# ESP-32-UNICLOCK-Nixi-V2.net
KiCad netlist of a schematic drawn in EAGLE
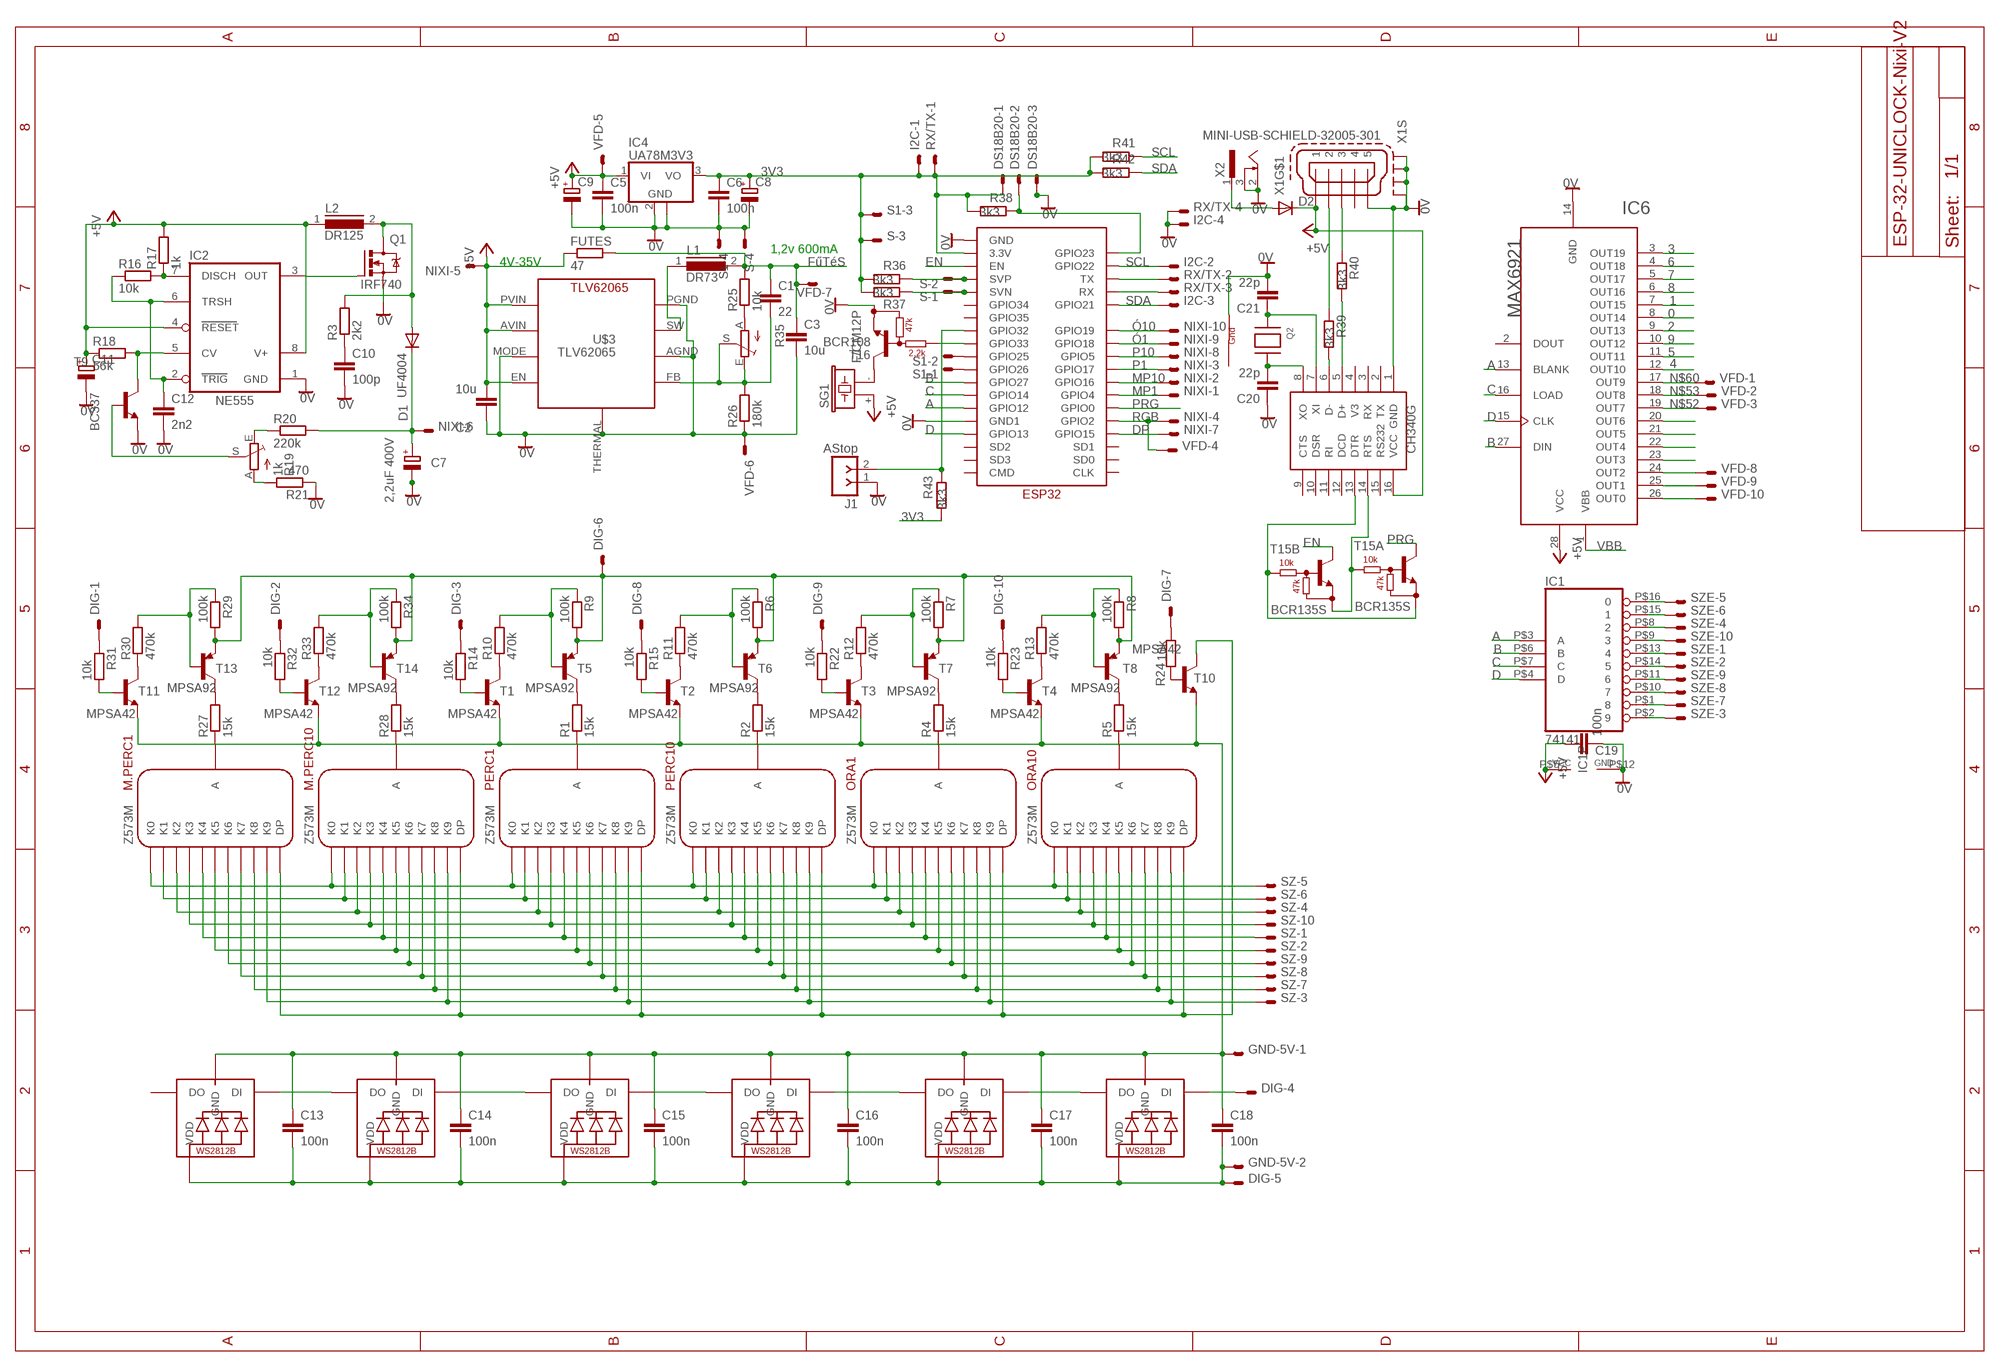
[diagram p0: schematic, sheet 1]

(export (version "E")
  (design (tool "Eeschema 10.0.6"))
  (components
    (comp (ref "C1")
      (value "22")
      (footprint "eagle-import:0603")
      (libsource (lib "eagle-import") (part "C0603"))
    )
    (comp (ref "C2")
      (value "10u")
      (footprint "eagle-import:1206")
      (libsource (lib "eagle-import") (part "C1206"))
    )
    (comp (ref "C3")
      (value "10u")
      (footprint "eagle-import:1206")
      (libsource (lib "eagle-import") (part "C1206"))
    )
    (comp (ref "C5")
      (value "100n")
      (footprint "eagle-import:0603")
      (libsource (lib "eagle-import") (part "C0603"))
    )
    (comp (ref "C6")
      (value "100n")
      (footprint "eagle-import:0603")
      (libsource (lib "eagle-import") (part "C0603"))
    )
    (comp (ref "C7")
      (value "2,2uF 400V")
      (footprint "eagle-import:E2,5-7")
      (libsource (lib "eagle-import") (part "CPOL-EUE2.5-7"))
    )
    (comp (ref "C8")
      (value "CPOL-EUE2.5-5")
      (footprint "eagle-import:E2,5-5")
      (libsource (lib "eagle-import") (part "CPOL-EUE2.5-5"))
    )
    (comp (ref "C9")
      (value "CPOL-EUE2.5-5")
      (footprint "eagle-import:E2,5-5")
      (libsource (lib "eagle-import") (part "CPOL-EUE2.5-5"))
    )
    (comp (ref "C10")
      (value "100p")
      (footprint "eagle-import:C050-024X044")
      (libsource (lib "eagle-import") (part "C-EU050-024X044"))
    )
    (comp (ref "C11")
      (value "CPOL-EUE2.5-7")
      (footprint "eagle-import:E2,5-7")
      (libsource (lib "eagle-import") (part "CPOL-EUE2.5-7"))
    )
    (comp (ref "C12")
      (value "2n2")
      (footprint "eagle-import:C0603")
      (libsource (lib "eagle-import") (part "C-EUC0603"))
    )
    (comp (ref "C13")
      (value "100n")
      (footprint "eagle-import:C0603")
      (libsource (lib "eagle-import") (part "C-EUC0603"))
    )
    (comp (ref "C14")
      (value "100n")
      (footprint "eagle-import:C0603")
      (libsource (lib "eagle-import") (part "C-EUC0603"))
    )
    (comp (ref "C15")
      (value "100n")
      (footprint "eagle-import:C0603")
      (libsource (lib "eagle-import") (part "C-EUC0603"))
    )
    (comp (ref "C16")
      (value "100n")
      (footprint "eagle-import:C0603")
      (libsource (lib "eagle-import") (part "C-EUC0603"))
    )
    (comp (ref "C17")
      (value "100n")
      (footprint "eagle-import:C0603")
      (libsource (lib "eagle-import") (part "C-EUC0603"))
    )
    (comp (ref "C18")
      (value "100n")
      (footprint "eagle-import:C0603")
      (libsource (lib "eagle-import") (part "C-EUC0603"))
    )
    (comp (ref "C19")
      (value "100n")
      (footprint "eagle-import:0603")
      (libsource (lib "eagle-import") (part "C0603"))
    )
    (comp (ref "C20")
      (value "22p")
      (footprint "eagle-import:0603")
      (libsource (lib "eagle-import") (part "C0603"))
    )
    (comp (ref "C21")
      (value "22p")
      (footprint "eagle-import:0603")
      (libsource (lib "eagle-import") (part "C0603"))
    )
    (comp (ref "D1")
      (value "UF4004")
      (footprint "eagle-import:DO35-10")
      (libsource (lib "eagle-import") (part "BA221"))
    )
    (comp (ref "D2")
      (value "DIODE-SOD123")
      (footprint "eagle-import:SOD123")
      (libsource (lib "eagle-import") (part "DIODE-SOD123"))
    )
    (comp (ref "DIG")
      (value "DIG")
      (footprint "eagle-import:PAD10")
      (libsource (lib "eagle-import") (part "PAD10"))
    )
    (comp (ref "DS18B20")
      (value "PAD3")
      (footprint "eagle-import:PAD3")
      (libsource (lib "eagle-import") (part "PAD3"))
    )
    (comp (ref "FUTES")
      (value "47")
      (footprint "eagle-import:0207_10")
      (libsource (lib "eagle-import") (part "R-EU_0207/10"))
    )
    (comp (ref "GND-5V")
      (value "PAD2")
      (footprint "eagle-import:PAD2")
      (libsource (lib "eagle-import") (part "PAD2"))
    )
    (comp (ref "I2C")
      (value "PAD4")
      (footprint "eagle-import:PAD4")
      (libsource (lib "eagle-import") (part "PAD4"))
    )
    (comp (ref "IC1")
      (value "74141")
      (footprint "eagle-import:DIL16SMD")
      (libsource (lib "eagle-import") (part "74141"))
    )
    (comp (ref "IC2")
      (value "NE555")
      (footprint "eagle-import:DIL08")
      (fields (field (name "MF") "MAXIM") (field (name "MPN") "ICM7555IPA+"))
      (libsource (lib "eagle-import") (part "ICM7555"))
    )
    (comp (ref "IC4")
      (value "UA78M3V3")
      (footprint "eagle-import:SOT223")
      (libsource (lib "eagle-import") (part "UA78MDCY05"))
    )
    (comp (ref "IC6")
      (value "MAX6921")
      (footprint "eagle-import:SO-28W")
      (libsource (lib "eagle-import") (part "MAX6921SOIC28W"))
    )
    (comp (ref "J1")
      (value "AStop")
      (footprint "eagle-import:SIP-100-02-32")
      (libsource (lib "eagle-import") (part "F-1X02-SIP-100-32"))
    )
    (comp (ref "L1")
      (value "DR73")
      (footprint "eagle-import:DR73")
      (libsource (lib "eagle-import") (part "DR73"))
    )
    (comp (ref "L2")
      (value "DR125")
      (footprint "eagle-import:DR125")
      (libsource (lib "eagle-import") (part "DR125"))
    )
    (comp (ref "LED1")
      (value "WS2812B_5050N")
      (footprint "eagle-import:WS2812B-NARROW")
      (libsource (lib "eagle-import") (part "WS2812B_5050N"))
    )
    (comp (ref "LED2")
      (value "WS2812B_5050N")
      (footprint "eagle-import:WS2812B-NARROW")
      (libsource (lib "eagle-import") (part "WS2812B_5050N"))
    )
    (comp (ref "LED3")
      (value "WS2812B_5050N")
      (footprint "eagle-import:WS2812B-NARROW")
      (libsource (lib "eagle-import") (part "WS2812B_5050N"))
    )
    (comp (ref "LED4")
      (value "WS2812B_5050N")
      (footprint "eagle-import:WS2812B-NARROW")
      (libsource (lib "eagle-import") (part "WS2812B_5050N"))
    )
    (comp (ref "LED5")
      (value "WS2812B_5050N")
      (footprint "eagle-import:WS2812B-NARROW")
      (libsource (lib "eagle-import") (part "WS2812B_5050N"))
    )
    (comp (ref "LED6")
      (value "WS2812B_5050N")
      (footprint "eagle-import:WS2812B-NARROW")
      (libsource (lib "eagle-import") (part "WS2812B_5050N"))
    )
    (comp (ref "M.PERC1")
      (value "MP1")
      (footprint "eagle-import:Z573SZ1")
      (libsource (lib "eagle-import") (part "Z573SZ1"))
    )
    (comp (ref "M.PERC10")
      (value "MP10")
      (footprint "eagle-import:Z573SZ1")
      (libsource (lib "eagle-import") (part "Z573SZ1"))
    )
    (comp (ref "NIXI")
      (value "PAD10")
      (footprint "eagle-import:PAD10")
      (libsource (lib "eagle-import") (part "PAD10"))
    )
    (comp (ref "ORA1")
      (value "O1")
      (footprint "eagle-import:Z573SZ1")
      (libsource (lib "eagle-import") (part "Z573SZ1"))
    )
    (comp (ref "ORA10")
      (value "O10")
      (footprint "eagle-import:Z573SZ1")
      (libsource (lib "eagle-import") (part "Z573SZ1"))
    )
    (comp (ref "PERC1")
      (value "P1")
      (footprint "eagle-import:Z573SZ1")
      (libsource (lib "eagle-import") (part "Z573SZ1"))
    )
    (comp (ref "PERC10")
      (value "P10")
      (footprint "eagle-import:Z573SZ1")
      (libsource (lib "eagle-import") (part "Z573SZ1"))
    )
    (comp (ref "Q1")
      (value "IRF740")
      (footprint "eagle-import:TO220BV")
      (libsource (lib "eagle-import") (part "IRF740"))
    )
    (comp (ref "Q2")
      (value "XTAL-4-3225")
      (footprint "eagle-import:NX3225")
      (libsource (lib "eagle-import") (part "XTAL-4-3225"))
    )
    (comp (ref "R1")
      (value "15k")
      (footprint "eagle-import:0207_7")
      (libsource (lib "eagle-import") (part "R-EU_0207/7"))
    )
    (comp (ref "R2")
      (value "15k")
      (footprint "eagle-import:0207_7")
      (libsource (lib "eagle-import") (part "R-EU_0207/7"))
    )
    (comp (ref "R3")
      (value "2k2")
      (footprint "eagle-import:0204_7")
      (libsource (lib "eagle-import") (part "R-EU_0204/7"))
    )
    (comp (ref "R4")
      (value "15k")
      (footprint "eagle-import:0207_7")
      (libsource (lib "eagle-import") (part "R-EU_0207/7"))
    )
    (comp (ref "R5")
      (value "15k")
      (footprint "eagle-import:0207_7")
      (libsource (lib "eagle-import") (part "R-EU_0207/7"))
    )
    (comp (ref "R6")
      (value "100k")
      (footprint "eagle-import:0207_7")
      (libsource (lib "eagle-import") (part "R-EU_0207/7"))
    )
    (comp (ref "R7")
      (value "100k")
      (footprint "eagle-import:0207_7")
      (libsource (lib "eagle-import") (part "R-EU_0207/7"))
    )
    (comp (ref "R8")
      (value "100k")
      (footprint "eagle-import:0207_7")
      (libsource (lib "eagle-import") (part "R-EU_0207/7"))
    )
    (comp (ref "R9")
      (value "100k")
      (footprint "eagle-import:0207_7")
      (libsource (lib "eagle-import") (part "R-EU_0207/7"))
    )
    (comp (ref "R10")
      (value "470k")
      (footprint "eagle-import:0207_7")
      (libsource (lib "eagle-import") (part "R-EU_0207/7"))
    )
    (comp (ref "R11")
      (value "470k")
      (footprint "eagle-import:0207_7")
      (libsource (lib "eagle-import") (part "R-EU_0207/7"))
    )
    (comp (ref "R12")
      (value "470k")
      (footprint "eagle-import:0207_7")
      (libsource (lib "eagle-import") (part "R-EU_0207/7"))
    )
    (comp (ref "R13")
      (value "470k")
      (footprint "eagle-import:0207_7")
      (libsource (lib "eagle-import") (part "R-EU_0207/7"))
    )
    (comp (ref "R14")
      (value "10k")
      (footprint "eagle-import:0207_7")
      (libsource (lib "eagle-import") (part "R-EU_0207/7"))
    )
    (comp (ref "R15")
      (value "10k")
      (footprint "eagle-import:0207_7")
      (libsource (lib "eagle-import") (part "R-EU_0207/7"))
    )
    (comp (ref "R16")
      (value "10k")
      (footprint "eagle-import:R0603")
      (libsource (lib "eagle-import") (part "R-EU_R0603"))
    )
    (comp (ref "R17")
      (value "1k")
      (footprint "eagle-import:R0603")
      (libsource (lib "eagle-import") (part "R-EU_R0603"))
    )
    (comp (ref "R18")
      (value "56k")
      (footprint "eagle-import:R0603")
      (libsource (lib "eagle-import") (part "R-EU_R0603"))
    )
    (comp (ref "R19")
      (value "1k")
      (footprint "eagle-import:CA6H")
      (libsource (lib "eagle-import") (part "TRIM_EU-CA6H"))
    )
    (comp (ref "R20")
      (value "220k")
      (footprint "eagle-import:0204_7")
      (libsource (lib "eagle-import") (part "R-EU_0204/7"))
    )
    (comp (ref "R21")
      (value "470")
      (footprint "eagle-import:0204_7")
      (libsource (lib "eagle-import") (part "R-EU_0204/7"))
    )
    (comp (ref "R22")
      (value "10k")
      (footprint "eagle-import:0207_7")
      (libsource (lib "eagle-import") (part "R-EU_0207/7"))
    )
    (comp (ref "R23")
      (value "10k")
      (footprint "eagle-import:0207_7")
      (libsource (lib "eagle-import") (part "R-EU_0207/7"))
    )
    (comp (ref "R24")
      (value "10k")
      (footprint "eagle-import:0207_7")
      (libsource (lib "eagle-import") (part "R-EU_0207/7"))
    )
    (comp (ref "R25")
      (value "10k")
      (footprint "eagle-import:0603")
      (libsource (lib "eagle-import") (part "R0603"))
    )
    (comp (ref "R26")
      (value "180k")
      (footprint "eagle-import:0603")
      (libsource (lib "eagle-import") (part "R0603"))
    )
    (comp (ref "R27")
      (value "15k")
      (footprint "eagle-import:0207_7")
      (libsource (lib "eagle-import") (part "R-EU_0207/7"))
    )
    (comp (ref "R28")
      (value "15k")
      (footprint "eagle-import:0207_7")
      (libsource (lib "eagle-import") (part "R-EU_0207/7"))
    )
    (comp (ref "R29")
      (value "100k")
      (footprint "eagle-import:0207_7")
      (libsource (lib "eagle-import") (part "R-EU_0207/7"))
    )
    (comp (ref "R30")
      (value "470k")
      (footprint "eagle-import:0207_7")
      (libsource (lib "eagle-import") (part "R-EU_0207/7"))
    )
    (comp (ref "R31")
      (value "10k")
      (footprint "eagle-import:0207_7")
      (libsource (lib "eagle-import") (part "R-EU_0207/7"))
    )
    (comp (ref "R32")
      (value "10k")
      (footprint "eagle-import:0207_7")
      (libsource (lib "eagle-import") (part "R-EU_0207/7"))
    )
    (comp (ref "R33")
      (value "470k")
      (footprint "eagle-import:0207_7")
      (libsource (lib "eagle-import") (part "R-EU_0207/7"))
    )
    (comp (ref "R34")
      (value "100k")
      (footprint "eagle-import:0207_7")
      (libsource (lib "eagle-import") (part "R-EU_0207/7"))
    )
    (comp (ref "R35")
      (value "TRIM_EU-B25P")
      (footprint "eagle-import:B25P")
      (libsource (lib "eagle-import") (part "TRIM_EU-B25P"))
    )
    (comp (ref "R36")
      (value "3k3")
      (footprint "eagle-import:0603")
      (libsource (lib "eagle-import") (part "R0603"))
    )
    (comp (ref "R37")
      (value "3k3")
      (footprint "eagle-import:0603")
      (libsource (lib "eagle-import") (part "R0603"))
    )
    (comp (ref "R38")
      (value "3k3")
      (footprint "eagle-import:0603")
      (libsource (lib "eagle-import") (part "R0603"))
    )
    (comp (ref "R39")
      (value "3k3")
      (footprint "eagle-import:0603")
      (libsource (lib "eagle-import") (part "R0603"))
    )
    (comp (ref "R40")
      (value "3k3")
      (footprint "eagle-import:0603")
      (libsource (lib "eagle-import") (part "R0603"))
    )
    (comp (ref "R41")
      (value "3k3")
      (footprint "eagle-import:0603")
      (libsource (lib "eagle-import") (part "R0603"))
    )
    (comp (ref "R42")
      (value "3k3")
      (footprint "eagle-import:0603")
      (libsource (lib "eagle-import") (part "R0603"))
    )
    (comp (ref "R43")
      (value "3k3")
      (footprint "eagle-import:0603")
      (libsource (lib "eagle-import") (part "R0603"))
    )
    (comp (ref "RX/TX")
      (value "PAD4")
      (footprint "eagle-import:PAD4")
      (libsource (lib "eagle-import") (part "PAD4"))
    )
    (comp (ref "S")
      (value "PAD4")
      (footprint "eagle-import:PAD4")
      (libsource (lib "eagle-import") (part "PAD4"))
    )
    (comp (ref "S1")
      (value "PAD4")
      (footprint "eagle-import:PAD4")
      (libsource (lib "eagle-import") (part "PAD4"))
    )
    (comp (ref "SG1")
      (value "F/CM12P")
      (footprint "eagle-import:F_CM12P")
      (libsource (lib "eagle-import") (part "F/CM12P"))
    )
    (comp (ref "SZ")
      (value "PAD10")
      (footprint "eagle-import:PAD10")
      (libsource (lib "eagle-import") (part "PAD10"))
    )
    (comp (ref "SZE")
      (value "PAD10")
      (footprint "eagle-import:PAD10")
      (libsource (lib "eagle-import") (part "PAD10"))
    )
    (comp (ref "T1")
      (value "MPSA42")
      (footprint "eagle-import:TO92-EBC")
      (libsource (lib "eagle-import") (part "-NPN-TO92-EBCBC317"))
    )
    (comp (ref "T2")
      (value "MPSA42")
      (footprint "eagle-import:TO92-EBC")
      (libsource (lib "eagle-import") (part "-NPN-TO92-EBCBC317"))
    )
    (comp (ref "T3")
      (value "MPSA42")
      (footprint "eagle-import:TO92-EBC")
      (libsource (lib "eagle-import") (part "-NPN-TO92-EBCBC317"))
    )
    (comp (ref "T4")
      (value "MPSA42")
      (footprint "eagle-import:TO92-EBC")
      (libsource (lib "eagle-import") (part "-NPN-TO92-EBCBC317"))
    )
    (comp (ref "T5")
      (value "MPSA92")
      (footprint "eagle-import:TO92-EBC")
      (libsource (lib "eagle-import") (part "-PNP-TO92-EBCBC328"))
    )
    (comp (ref "T6")
      (value "MPSA92")
      (footprint "eagle-import:TO92-EBC")
      (libsource (lib "eagle-import") (part "-PNP-TO92-EBCBC328"))
    )
    (comp (ref "T7")
      (value "MPSA92")
      (footprint "eagle-import:TO92-EBC")
      (libsource (lib "eagle-import") (part "-PNP-TO92-EBCBC328"))
    )
    (comp (ref "T8")
      (value "MPSA92")
      (footprint "eagle-import:TO92-EBC")
      (libsource (lib "eagle-import") (part "-PNP-TO92-EBCBC328"))
    )
    (comp (ref "T9")
      (value "BC337")
      (footprint "eagle-import:TO92-CBE")
      (libsource (lib "eagle-import") (part "-NPN-TO92-CBEBC237"))
    )
    (comp (ref "T10")
      (value "MPSA42")
      (footprint "eagle-import:TO92-EBC")
      (libsource (lib "eagle-import") (part "-NPN-TO92-EBCBC317"))
    )
    (comp (ref "T11")
      (value "MPSA42")
      (footprint "eagle-import:TO92-EBC")
      (libsource (lib "eagle-import") (part "-NPN-TO92-EBCBC317"))
    )
    (comp (ref "T12")
      (value "MPSA42")
      (footprint "eagle-import:TO92-EBC")
      (libsource (lib "eagle-import") (part "-NPN-TO92-EBCBC317"))
    )
    (comp (ref "T13")
      (value "MPSA92")
      (footprint "eagle-import:TO92-EBC")
      (libsource (lib "eagle-import") (part "-PNP-TO92-EBCBC328"))
    )
    (comp (ref "T14")
      (value "MPSA92")
      (footprint "eagle-import:TO92-EBC")
      (libsource (lib "eagle-import") (part "-PNP-TO92-EBCBC328"))
    )
    (comp (ref "T15")
      (value "BCR135S")
      (footprint "eagle-import:SOT363_INFINEON")
      (libsource (lib "eagle-import") (part "BCR135S"))
    )
    (comp (ref "T16")
      (value "BCR108")
      (footprint "eagle-import:SOT23-BEC")
      (libsource (lib "eagle-import") (part "BCR108"))
    )
    (comp (ref "U$1")
      (value "CH340G")
      (footprint "eagle-import:SOIC16")
      (libsource (lib "eagle-import") (part "CH340G"))
    )
    (comp (ref "U$2")
      (value "ESP32-2X18")
      (footprint "eagle-import:ESP322X18")
      (libsource (lib "eagle-import") (part "ESP32-2X18"))
    )
    (comp (ref "U$3")
      (value "TLV62065")
      (footprint "eagle-import:TLV62065")
      (libsource (lib "eagle-import") (part "TLV62065"))
    )
    (comp (ref "VFD")
      (value "PAD10")
      (footprint "eagle-import:PAD10")
      (libsource (lib "eagle-import") (part "PAD10"))
    )
    (comp (ref "X1")
      (value "MINI-USB-SCHIELD-32005-301")
      (footprint "eagle-import:32005-301")
      (libsource (lib "eagle-import") (part "MINI-USB-SCHIELD-32005-301"))
    )
    (comp (ref "X2")
      (value "733989-5")
      (footprint "eagle-import:733989-5")
      (libsource (lib "eagle-import") (part "73398?9-5"))
    )
  )
  (nets
    (net (code "1") (name "+5V") (class "Default")
      (node (ref "C11") (pin "+") (pinfunction "+_+") (pintype "passive"))
      (node (ref "C19") (pin "1") (pinfunction "1_1") (pintype "passive"))
      (node (ref "C2") (pin "1") (pinfunction "1_1") (pintype "passive"))
      (node (ref "C5") (pin "1") (pinfunction "1_1") (pintype "passive"))
      (node (ref "C9") (pin "+") (pinfunction "+_+") (pintype "passive"))
      (node (ref "D2") (pin "C") (pinfunction "C_C") (pintype "passive"))
      (node (ref "FUTES") (pin "1") (pinfunction "1_1") (pintype "passive"))
      (node (ref "IC1") (pin "P$5") (pinfunction "VCC_P$5") (pintype "power_in"))
      (node (ref "IC2") (pin "4") (pinfunction "RESET_4") (pintype "input"))
      (node (ref "IC2") (pin "8") (pinfunction "V+_8") (pintype "power_in"))
      (node (ref "IC4") (pin "1") (pinfunction "VI_1") (pintype "input"))
      (node (ref "IC6") (pin "28") (pinfunction "VCC_28") (pintype "power_in"))
      (node (ref "L2") (pin "1") (pinfunction "1_1") (pintype "passive"))
      (node (ref "NIXI") (pin "P$5") (pinfunction "S_P$5") (pintype "passive"))
      (node (ref "R17") (pin "2") (pinfunction "2_2") (pintype "passive"))
      (node (ref "R18") (pin "1") (pinfunction "1_1") (pintype "passive"))
      (node (ref "SG1") (pin "+") (pinfunction "1_+") (pintype "passive"))
      (node (ref "U$1") (pin "16") (pinfunction "VCC_16") (pintype "bidirectional"))
      (node (ref "U$3") (pin "AVIN") (pinfunction "AVIN_AVIN") (pintype "bidirectional"))
      (node (ref "U$3") (pin "EN") (pinfunction "EN_EN") (pintype "bidirectional"))
      (node (ref "U$3") (pin "PVIN") (pinfunction "PVIN_PVIN") (pintype "bidirectional"))
      (node (ref "VFD") (pin "P$5") (pinfunction "S_P$5") (pintype "passive"))
      (node (ref "X1") (pin "1") (pinfunction "1_1") (pintype "passive"))
    )
    (net (code "2") (name "/0") (class "Default")
      (node (ref "IC1") (pin "P$16") (pinfunction "0_P$16") (pintype "open_collector"))
      (node (ref "IC6") (pin "8") (pinfunction "OUT14_8") (pintype "output"))
      (node (ref "SZE") (pin "P$5") (pinfunction "S_P$5") (pintype "passive"))
    )
    (net (code "3") (name "/1") (class "Default")
      (node (ref "IC1") (pin "P$15") (pinfunction "1_P$15") (pintype "open_collector"))
      (node (ref "IC6") (pin "7") (pinfunction "OUT15_7") (pintype "output"))
      (node (ref "SZE") (pin "P$6") (pinfunction "S_P$6") (pintype "passive"))
    )
    (net (code "4") (name "/2") (class "Default")
      (node (ref "IC1") (pin "P$8") (pinfunction "2_P$8") (pintype "open_collector"))
      (node (ref "IC6") (pin "9") (pinfunction "OUT13_9") (pintype "output"))
      (node (ref "SZE") (pin "P$4") (pinfunction "S_P$4") (pintype "passive"))
    )
    (net (code "5") (name "/3") (class "Default")
      (node (ref "IC1") (pin "P$9") (pinfunction "3_P$9") (pintype "open_collector"))
      (node (ref "IC6") (pin "3") (pinfunction "OUT19_3") (pintype "output"))
      (node (ref "SZE") (pin "P$10") (pinfunction "S_P$10") (pintype "passive"))
    )
    (net (code "6") (name "/3V3") (class "Default")
      (node (ref "C6") (pin "1") (pinfunction "1_1") (pintype "passive"))
      (node (ref "C8") (pin "+") (pinfunction "+_+") (pintype "passive"))
      (node (ref "DS18B20") (pin "P$1") (pinfunction "S_P$1") (pintype "passive"))
      (node (ref "I2C") (pin "P$1") (pinfunction "S_P$1") (pintype "passive"))
      (node (ref "IC4") (pin "3") (pinfunction "VO_3") (pintype "passive"))
      (node (ref "R36") (pin "2") (pinfunction "2_2") (pintype "passive"))
      (node (ref "R37") (pin "2") (pinfunction "2_2") (pintype "passive"))
      (node (ref "R38") (pin "2") (pinfunction "2_2") (pintype "passive"))
      (node (ref "R41") (pin "2") (pinfunction "2_2") (pintype "passive"))
      (node (ref "R42") (pin "2") (pinfunction "2_2") (pintype "passive"))
      (node (ref "R43") (pin "2") (pinfunction "2_2") (pintype "passive"))
      (node (ref "RX/TX") (pin "P$1") (pinfunction "S_P$1") (pintype "passive"))
      (node (ref "S") (pin "P$3") (pinfunction "S_P$3") (pintype "passive"))
      (node (ref "S1") (pin "P$3") (pinfunction "S_P$3") (pintype "passive"))
      (node (ref "U$2") (pin "P$20") (pinfunction "3.3V_P$20") (pintype "bidirectional"))
    )
    (net (code "7") (name "/4") (class "Default")
      (node (ref "IC1") (pin "P$13") (pinfunction "4_P$13") (pintype "open_collector"))
      (node (ref "IC6") (pin "12") (pinfunction "OUT10_12") (pintype "output"))
      (node (ref "SZE") (pin "P$1") (pinfunction "S_P$1") (pintype "passive"))
    )
    (net (code "8") (name "/5") (class "Default")
      (node (ref "IC1") (pin "P$14") (pinfunction "5_P$14") (pintype "open_collector"))
      (node (ref "IC6") (pin "11") (pinfunction "OUT11_11") (pintype "output"))
      (node (ref "SZE") (pin "P$2") (pinfunction "S_P$2") (pintype "passive"))
    )
    (net (code "9") (name "/6") (class "Default")
      (node (ref "IC1") (pin "P$11") (pinfunction "6_P$11") (pintype "open_collector"))
      (node (ref "IC6") (pin "4") (pinfunction "OUT18_4") (pintype "output"))
      (node (ref "SZE") (pin "P$9") (pinfunction "S_P$9") (pintype "passive"))
    )
    (net (code "10") (name "/7") (class "Default")
      (node (ref "IC1") (pin "P$10") (pinfunction "7_P$10") (pintype "open_collector"))
      (node (ref "IC6") (pin "5") (pinfunction "OUT17_5") (pintype "output"))
      (node (ref "SZE") (pin "P$8") (pinfunction "S_P$8") (pintype "passive"))
    )
    (net (code "11") (name "/8") (class "Default")
      (node (ref "IC1") (pin "P$1") (pinfunction "8_P$1") (pintype "open_collector"))
      (node (ref "IC6") (pin "6") (pinfunction "OUT16_6") (pintype "output"))
      (node (ref "SZE") (pin "P$7") (pinfunction "S_P$7") (pintype "passive"))
    )
    (net (code "12") (name "/9") (class "Default")
      (node (ref "IC1") (pin "P$2") (pinfunction "9_P$2") (pintype "open_collector"))
      (node (ref "IC6") (pin "10") (pinfunction "OUT12_10") (pintype "output"))
      (node (ref "SZE") (pin "P$3") (pinfunction "S_P$3") (pintype "passive"))
    )
    (net (code "13") (name "/A") (class "Default")
      (node (ref "IC1") (pin "P$3") (pinfunction "A_P$3") (pintype "input"))
      (node (ref "IC6") (pin "13") (pinfunction "BLANK_13") (pintype "input"))
      (node (ref "U$2") (pin "P$12") (pinfunction "GPIO12_P$12") (pintype "bidirectional"))
    )
    (net (code "14") (name "/B") (class "Default")
      (node (ref "IC1") (pin "P$6") (pinfunction "B_P$6") (pintype "input"))
      (node (ref "IC6") (pin "27") (pinfunction "DIN_27") (pintype "input"))
      (node (ref "U$2") (pin "P$10") (pinfunction "GPIO27_P$10") (pintype "bidirectional"))
    )
    (net (code "15") (name "/C") (class "Default")
      (node (ref "IC1") (pin "P$7") (pinfunction "C_P$7") (pintype "input"))
      (node (ref "IC6") (pin "16") (pinfunction "LOAD_16") (pintype "input"))
      (node (ref "U$2") (pin "P$9") (pinfunction "GPIO14_P$9") (pintype "bidirectional"))
    )
    (net (code "16") (name "/D") (class "Default")
      (node (ref "IC1") (pin "P$4") (pinfunction "D_P$4") (pintype "input"))
      (node (ref "IC6") (pin "15") (pinfunction "CLK_15") (pintype "input"))
      (node (ref "U$2") (pin "P$11") (pinfunction "GPIO13_P$11") (pintype "bidirectional"))
    )
    (net (code "17") (name "/DP") (class "Default")
      (node (ref "NIXI") (pin "P$7") (pinfunction "S_P$7") (pintype "passive"))
      (node (ref "U$2") (pin "P$35") (pinfunction "GPIO15_P$35") (pintype "bidirectional"))
    )
    (net (code "18") (name "/EN") (class "Default")
      (node (ref "T15") (pin "3") (pinfunction "C_3") (pintype "passive"))
      (node (ref "U$2") (pin "P$21") (pinfunction "EN_P$21") (pintype "bidirectional"))
    )
    (net (code "19") (name "/FűTéS") (class "Default")
      (node (ref "C1") (pin "1") (pinfunction "1_1") (pintype "passive"))
      (node (ref "C3") (pin "1") (pinfunction "1_1") (pintype "passive"))
      (node (ref "FUTES") (pin "2") (pinfunction "2_2") (pintype "passive"))
      (node (ref "L1") (pin "2") (pinfunction "2_2") (pintype "passive"))
      (node (ref "R25") (pin "2") (pinfunction "2_2") (pintype "passive"))
      (node (ref "VFD") (pin "P$7") (pinfunction "S_P$7") (pintype "passive"))
    )
    (net (code "20") (name "/G2") (class "Default")
      (node (ref "Q2") (pin "2") (pinfunction "G2_2") (pintype "power_in"))
    )
    (net (code "21") (name "/MP1") (class "Default")
      (node (ref "NIXI") (pin "P$1") (pinfunction "S_P$1") (pintype "passive"))
      (node (ref "U$2") (pin "P$34") (pinfunction "GPIO4_P$34") (pintype "bidirectional"))
    )
    (net (code "22") (name "/MP10") (class "Default")
      (node (ref "NIXI") (pin "P$2") (pinfunction "S_P$2") (pintype "passive"))
      (node (ref "U$2") (pin "P$31") (pinfunction "GPIO16_P$31") (pintype "bidirectional"))
    )
    (net (code "23") (name "/N$52") (class "Default")
      (node (ref "IC6") (pin "19") (pinfunction "OUT7_19") (pintype "output"))
      (node (ref "VFD") (pin "P$3") (pinfunction "S_P$3") (pintype "passive"))
    )
    (net (code "24") (name "/N$53") (class "Default")
      (node (ref "IC6") (pin "18") (pinfunction "OUT8_18") (pintype "output"))
      (node (ref "VFD") (pin "P$2") (pinfunction "S_P$2") (pintype "passive"))
    )
    (net (code "25") (name "/N$60") (class "Default")
      (node (ref "IC6") (pin "17") (pinfunction "OUT9_17") (pintype "output"))
      (node (ref "VFD") (pin "P$1") (pinfunction "S_P$1") (pintype "passive"))
    )
    (net (code "26") (name "/P1") (class "Default")
      (node (ref "NIXI") (pin "P$3") (pinfunction "S_P$3") (pintype "passive"))
      (node (ref "U$2") (pin "P$32") (pinfunction "GPIO17_P$32") (pintype "bidirectional"))
    )
    (net (code "27") (name "/P10") (class "Default")
      (node (ref "NIXI") (pin "P$8") (pinfunction "S_P$8") (pintype "passive"))
      (node (ref "U$2") (pin "P$29") (pinfunction "GPIO5_P$29") (pintype "bidirectional"))
    )
    (net (code "28") (name "/PRG") (class "Default")
      (node (ref "T15") (pin "6") (pinfunction "C_6") (pintype "passive"))
      (node (ref "U$2") (pin "P$33") (pinfunction "GPIO0_P$33") (pintype "bidirectional"))
    )
    (net (code "29") (name "/RGB") (class "Default")
      (node (ref "NIXI") (pin "P$4") (pinfunction "S_P$4") (pintype "passive"))
      (node (ref "U$2") (pin "P$36") (pinfunction "GPIO2_P$36") (pintype "bidirectional"))
      (node (ref "VFD") (pin "P$4") (pinfunction "S_P$4") (pintype "passive"))
    )
    (net (code "30") (name "/SCL") (class "Default")
      (node (ref "I2C") (pin "P$2") (pinfunction "S_P$2") (pintype "passive"))
      (node (ref "R41") (pin "1") (pinfunction "1_1") (pintype "passive"))
      (node (ref "U$2") (pin "P$25") (pinfunction "GPIO22_P$25") (pintype "bidirectional"))
    )
    (net (code "31") (name "/SDA") (class "Default")
      (node (ref "I2C") (pin "P$3") (pinfunction "S_P$3") (pintype "passive"))
      (node (ref "R42") (pin "1") (pinfunction "1_1") (pintype "passive"))
      (node (ref "U$2") (pin "P$28") (pinfunction "GPIO21_P$28") (pintype "bidirectional"))
    )
    (net (code "32") (name "/VBB") (class "Default")
      (node (ref "C7") (pin "+") (pinfunction "+_+") (pintype "passive"))
      (node (ref "D1") (pin "C") (pinfunction "C_C") (pintype "passive"))
      (node (ref "IC6") (pin "1") (pinfunction "VBB_1") (pintype "power_in"))
      (node (ref "NIXI") (pin "P$6") (pinfunction "S_P$6") (pintype "passive"))
      (node (ref "R20") (pin "2") (pinfunction "2_2") (pintype "passive"))
    )
    (net (code "33") (name "/Ó1") (class "Default")
      (node (ref "NIXI") (pin "P$9") (pinfunction "S_P$9") (pintype "passive"))
      (node (ref "U$2") (pin "P$30") (pinfunction "GPIO18_P$30") (pintype "bidirectional"))
    )
    (net (code "34") (name "/Ó10") (class "Default")
      (node (ref "NIXI") (pin "P$10") (pinfunction "S_P$10") (pintype "passive"))
      (node (ref "U$2") (pin "P$27") (pinfunction "GPIO19_P$27") (pintype "bidirectional"))
    )
    (net (code "35") (name "0V") (class "Default")
      (node (ref "C10") (pin "2") (pinfunction "2_2") (pintype "passive"))
      (node (ref "C11") (pin "-") (pinfunction "-_-") (pintype "passive"))
      (node (ref "C12") (pin "2") (pinfunction "2_2") (pintype "passive"))
      (node (ref "C19") (pin "2") (pinfunction "2_2") (pintype "passive"))
      (node (ref "C2") (pin "2") (pinfunction "2_2") (pintype "passive"))
      (node (ref "C20") (pin "1") (pinfunction "1_1") (pintype "passive"))
      (node (ref "C21") (pin "2") (pinfunction "2_2") (pintype "passive"))
      (node (ref "C3") (pin "2") (pinfunction "2_2") (pintype "passive"))
      (node (ref "C5") (pin "2") (pinfunction "2_2") (pintype "passive"))
      (node (ref "C6") (pin "2") (pinfunction "2_2") (pintype "passive"))
      (node (ref "C7") (pin "-") (pinfunction "-_-") (pintype "passive"))
      (node (ref "C8") (pin "-") (pinfunction "-_-") (pintype "passive"))
      (node (ref "C9") (pin "-") (pinfunction "-_-") (pintype "passive"))
      (node (ref "DS18B20") (pin "P$3") (pinfunction "S_P$3") (pintype "passive"))
      (node (ref "I2C") (pin "P$4") (pinfunction "S_P$4") (pintype "passive"))
      (node (ref "IC1") (pin "P$12") (pinfunction "GND_P$12") (pintype "power_in"))
      (node (ref "IC2") (pin "1") (pinfunction "GND_1") (pintype "power_in"))
      (node (ref "IC4") (pin "2") (pinfunction "GND_2") (pintype "passive"))
      (node (ref "IC4") (pin "4") (pinfunction "GND_4") (pintype "passive"))
      (node (ref "IC6") (pin "14") (pinfunction "GND_14") (pintype "power_in"))
      (node (ref "J1") (pin "1") (pinfunction "1_1") (pintype "passive"))
      (node (ref "Q1") (pin "S") (pinfunction "S_S") (pintype "passive"))
      (node (ref "Q2") (pin "4") (pinfunction "G1_4") (pintype "power_in"))
      (node (ref "R21") (pin "1") (pinfunction "1_1") (pintype "passive"))
      (node (ref "R26") (pin "1") (pinfunction "1_1") (pintype "passive"))
      (node (ref "RX/TX") (pin "P$4") (pinfunction "S_P$4") (pintype "passive"))
      (node (ref "S") (pin "P$4") (pinfunction "S_P$4") (pintype "passive"))
      (node (ref "S1") (pin "P$4") (pinfunction "S_P$4") (pintype "passive"))
      (node (ref "T16") (pin "E") (pinfunction "E_E") (pintype "passive"))
      (node (ref "T9") (pin "E") (pinfunction "E_E") (pintype "passive"))
      (node (ref "U$1") (pin "1") (pinfunction "GND_1") (pintype "bidirectional"))
      (node (ref "U$2") (pin "P$19") (pinfunction "GND_P$19") (pintype "bidirectional"))
      (node (ref "U$2") (pin "P$26") (pinfunction "GND1_P$26") (pintype "bidirectional"))
      (node (ref "U$3") (pin "AGND") (pinfunction "AGND_AGND") (pintype "bidirectional"))
      (node (ref "U$3") (pin "MODE") (pinfunction "MODE_MODE") (pintype "bidirectional"))
      (node (ref "U$3") (pin "PGND") (pinfunction "PGND_PGND") (pintype "bidirectional"))
      (node (ref "U$3") (pin "THERMAL") (pinfunction "THERMAL_THERMAL") (pintype "bidirectional"))
      (node (ref "VFD") (pin "P$6") (pinfunction "S_P$6") (pintype "passive"))
      (node (ref "X1") (pin "5") (pinfunction "5_5") (pintype "passive"))
      (node (ref "X1") (pin "M1") (pinfunction "S1_M1") (pintype "passive"))
      (node (ref "X1") (pin "M2") (pinfunction "S2_M2") (pintype "passive"))
      (node (ref "X1") (pin "M3") (pinfunction "S3_M3") (pintype "passive"))
      (node (ref "X1") (pin "M4") (pinfunction "S4_M4") (pintype "passive"))
      (node (ref "X2") (pin "2") (pinfunction "2_2") (pintype "passive"))
      (node (ref "X2") (pin "3") (pinfunction "3_3") (pintype "passive"))
    )
    (net (code "36") (name "Net-(C1-Pad2)") (class "Default")
      (node (ref "C1") (pin "2") (pinfunction "2_2") (pintype "passive"))
      (node (ref "R26") (pin "2") (pinfunction "2_2") (pintype "passive"))
      (node (ref "R35") (pin "E") (pinfunction "E_E") (pintype "passive"))
      (node (ref "R35") (pin "S") (pinfunction "S_S") (pintype "passive"))
      (node (ref "U$3") (pin "FB") (pinfunction "FB_FB") (pintype "bidirectional"))
    )
    (net (code "37") (name "Net-(C10-Pad1)") (class "Default")
      (node (ref "C10") (pin "1") (pinfunction "1_1") (pintype "passive"))
      (node (ref "R3") (pin "1") (pinfunction "1_1") (pintype "passive"))
    )
    (net (code "38") (name "Net-(D1-PadA)") (class "Default")
      (node (ref "D1") (pin "A") (pinfunction "A_A") (pintype "passive"))
      (node (ref "L2") (pin "2") (pinfunction "2_2") (pintype "passive"))
      (node (ref "Q1") (pin "D") (pinfunction "D_D") (pintype "passive"))
      (node (ref "R3") (pin "2") (pinfunction "2_2") (pintype "passive"))
    )
    (net (code "39") (name "Net-(D2-PadA)") (class "Default")
      (node (ref "D2") (pin "A") (pinfunction "A_A") (pintype "passive"))
      (node (ref "X2") (pin "1") (pinfunction "1_1") (pintype "passive"))
    )
    (net (code "40") (name "Net-(DIGA-S)") (class "Default")
      (node (ref "DIG") (pin "P$1") (pinfunction "S_P$1") (pintype "passive"))
      (node (ref "R31") (pin "1") (pinfunction "1_1") (pintype "passive"))
    )
    (net (code "41") (name "Net-(DIGB-S)") (class "Default")
      (node (ref "DIG") (pin "P$10") (pinfunction "S_P$10") (pintype "passive"))
      (node (ref "R23") (pin "1") (pinfunction "1_1") (pintype "passive"))
    )
    (net (code "42") (name "Net-(DIGC-S)") (class "Default")
      (node (ref "DIG") (pin "P$2") (pinfunction "S_P$2") (pintype "passive"))
      (node (ref "R32") (pin "1") (pinfunction "1_1") (pintype "passive"))
    )
    (net (code "43") (name "Net-(DIGD-S)") (class "Default")
      (node (ref "DIG") (pin "P$3") (pinfunction "S_P$3") (pintype "passive"))
      (node (ref "R14") (pin "1") (pinfunction "1_1") (pintype "passive"))
    )
    (net (code "44") (name "Net-(DIGE-S)") (class "Default")
      (node (ref "DIG") (pin "P$4") (pinfunction "S_P$4") (pintype "passive"))
      (node (ref "LED1") (pin "4-DIN") (pinfunction "DI_4-DIN") (pintype "input"))
    )
    (net (code "45") (name "Net-(DIGF-S)") (class "Default")
      (node (ref "C13") (pin "2") (pinfunction "2_2") (pintype "passive"))
      (node (ref "C14") (pin "2") (pinfunction "2_2") (pintype "passive"))
      (node (ref "C15") (pin "2") (pinfunction "2_2") (pintype "passive"))
      (node (ref "C16") (pin "2") (pinfunction "2_2") (pintype "passive"))
      (node (ref "C17") (pin "2") (pinfunction "2_2") (pintype "passive"))
      (node (ref "C18") (pin "2") (pinfunction "2_2") (pintype "passive"))
      (node (ref "DIG") (pin "P$5") (pinfunction "S_P$5") (pintype "passive"))
      (node (ref "GND-5V") (pin "P$2") (pinfunction "S_P$2") (pintype "passive"))
      (node (ref "LED1") (pin "1-VDD") (pinfunction "VDD_1-VDD") (pintype "power_in"))
      (node (ref "LED2") (pin "1-VDD") (pinfunction "VDD_1-VDD") (pintype "power_in"))
      (node (ref "LED3") (pin "1-VDD") (pinfunction "VDD_1-VDD") (pintype "power_in"))
      (node (ref "LED4") (pin "1-VDD") (pinfunction "VDD_1-VDD") (pintype "power_in"))
      (node (ref "LED5") (pin "1-VDD") (pinfunction "VDD_1-VDD") (pintype "power_in"))
      (node (ref "LED6") (pin "1-VDD") (pinfunction "VDD_1-VDD") (pintype "power_in"))
    )
    (net (code "46") (name "Net-(DIGG-S)") (class "Default")
      (node (ref "DIG") (pin "P$6") (pinfunction "S_P$6") (pintype "passive"))
      (node (ref "R29") (pin "2") (pinfunction "2_2") (pintype "passive"))
      (node (ref "R34") (pin "2") (pinfunction "2_2") (pintype "passive"))
      (node (ref "R6") (pin "2") (pinfunction "2_2") (pintype "passive"))
      (node (ref "R7") (pin "2") (pinfunction "2_2") (pintype "passive"))
      (node (ref "R8") (pin "2") (pinfunction "2_2") (pintype "passive"))
      (node (ref "R9") (pin "2") (pinfunction "2_2") (pintype "passive"))
      (node (ref "T13") (pin "E") (pinfunction "E_E") (pintype "passive"))
      (node (ref "T14") (pin "E") (pinfunction "E_E") (pintype "passive"))
      (node (ref "T5") (pin "E") (pinfunction "E_E") (pintype "passive"))
      (node (ref "T6") (pin "E") (pinfunction "E_E") (pintype "passive"))
      (node (ref "T7") (pin "E") (pinfunction "E_E") (pintype "passive"))
      (node (ref "T8") (pin "E") (pinfunction "E_E") (pintype "passive"))
    )
    (net (code "47") (name "Net-(DIGH-S)") (class "Default")
      (node (ref "DIG") (pin "P$7") (pinfunction "S_P$7") (pintype "passive"))
      (node (ref "R24") (pin "1") (pinfunction "1_1") (pintype "passive"))
    )
    (net (code "48") (name "Net-(DIGI-S)") (class "Default")
      (node (ref "DIG") (pin "P$8") (pinfunction "S_P$8") (pintype "passive"))
      (node (ref "R15") (pin "1") (pinfunction "1_1") (pintype "passive"))
    )
    (net (code "49") (name "Net-(DIGJ-S)") (class "Default")
      (node (ref "DIG") (pin "P$9") (pinfunction "S_P$9") (pintype "passive"))
      (node (ref "R22") (pin "1") (pinfunction "1_1") (pintype "passive"))
    )
    (net (code "50") (name "Net-(DS18B20B-S)") (class "Default")
      (node (ref "DS18B20") (pin "P$2") (pinfunction "S_P$2") (pintype "passive"))
      (node (ref "R38") (pin "1") (pinfunction "1_1") (pintype "passive"))
      (node (ref "U$2") (pin "P$23") (pinfunction "GPIO23_P$23") (pintype "bidirectional"))
    )
    (net (code "51") (name "Net-(GND-5VA-S)") (class "Default")
      (node (ref "C13") (pin "1") (pinfunction "1_1") (pintype "passive"))
      (node (ref "C14") (pin "1") (pinfunction "1_1") (pintype "passive"))
      (node (ref "C15") (pin "1") (pinfunction "1_1") (pintype "passive"))
      (node (ref "C16") (pin "1") (pinfunction "1_1") (pintype "passive"))
      (node (ref "C17") (pin "1") (pinfunction "1_1") (pintype "passive"))
      (node (ref "C18") (pin "1") (pinfunction "1_1") (pintype "passive"))
      (node (ref "GND-5V") (pin "P$1") (pinfunction "S_P$1") (pintype "passive"))
      (node (ref "LED1") (pin "3-GND") (pinfunction "GND_3-GND") (pintype "power_in"))
      (node (ref "LED2") (pin "3-GND") (pinfunction "GND_3-GND") (pintype "power_in"))
      (node (ref "LED3") (pin "3-GND") (pinfunction "GND_3-GND") (pintype "power_in"))
      (node (ref "LED4") (pin "3-GND") (pinfunction "GND_3-GND") (pintype "power_in"))
      (node (ref "LED5") (pin "3-GND") (pinfunction "GND_3-GND") (pintype "power_in"))
      (node (ref "LED6") (pin "3-GND") (pinfunction "GND_3-GND") (pintype "power_in"))
      (node (ref "T1") (pin "E") (pinfunction "E_E") (pintype "passive"))
      (node (ref "T10") (pin "E") (pinfunction "E_E") (pintype "passive"))
      (node (ref "T11") (pin "E") (pinfunction "E_E") (pintype "passive"))
      (node (ref "T12") (pin "E") (pinfunction "E_E") (pintype "passive"))
      (node (ref "T2") (pin "E") (pinfunction "E_E") (pintype "passive"))
      (node (ref "T3") (pin "E") (pinfunction "E_E") (pintype "passive"))
      (node (ref "T4") (pin "E") (pinfunction "E_E") (pintype "passive"))
    )
    (net (code "52") (name "Net-(IC2-CV)") (class "Default")
      (node (ref "IC2") (pin "5") (pinfunction "CV_5") (pintype "passive"))
      (node (ref "R18") (pin "2") (pinfunction "2_2") (pintype "passive"))
      (node (ref "T9") (pin "C") (pinfunction "C_C") (pintype "passive"))
    )
    (net (code "53") (name "Net-(IC2-DISCH)") (class "Default")
      (node (ref "IC2") (pin "7") (pinfunction "DISCH_7") (pintype "input"))
      (node (ref "R16") (pin "2") (pinfunction "2_2") (pintype "passive"))
      (node (ref "R17") (pin "1") (pinfunction "1_1") (pintype "passive"))
    )
    (net (code "54") (name "Net-(IC2-OUT)") (class "Default")
      (node (ref "IC2") (pin "3") (pinfunction "OUT_3") (pintype "output"))
      (node (ref "Q1") (pin "G") (pinfunction "G_G") (pintype "passive"))
    )
    (net (code "55") (name "Net-(IC2-TRIG)") (class "Default")
      (node (ref "C12") (pin "1") (pinfunction "1_1") (pintype "passive"))
      (node (ref "IC2") (pin "2") (pinfunction "TRIG_2") (pintype "bidirectional"))
      (node (ref "IC2") (pin "6") (pinfunction "TRSH_6") (pintype "input"))
      (node (ref "R16") (pin "1") (pinfunction "1_1") (pintype "passive"))
    )
    (net (code "56") (name "Net-(IC6-OUT0)") (class "Default")
      (node (ref "IC6") (pin "26") (pinfunction "OUT0_26") (pintype "output"))
      (node (ref "VFD") (pin "P$10") (pinfunction "S_P$10") (pintype "passive"))
    )
    (net (code "57") (name "Net-(IC6-OUT1)") (class "Default")
      (node (ref "IC6") (pin "25") (pinfunction "OUT1_25") (pintype "output"))
      (node (ref "VFD") (pin "P$9") (pinfunction "S_P$9") (pintype "passive"))
    )
    (net (code "58") (name "Net-(IC6-OUT2)") (class "Default")
      (node (ref "IC6") (pin "24") (pinfunction "OUT2_24") (pintype "output"))
      (node (ref "VFD") (pin "P$8") (pinfunction "S_P$8") (pintype "passive"))
    )
    (net (code "59") (name "Net-(L1-Pad1)") (class "Default")
      (node (ref "L1") (pin "1") (pinfunction "1_1") (pintype "passive"))
      (node (ref "U$3") (pin "SW") (pinfunction "SW_SW") (pintype "bidirectional"))
    )
    (net (code "60") (name "Net-(LED1-DO)") (class "Default")
      (node (ref "LED1") (pin "2-DOUT") (pinfunction "DO_2-DOUT") (pintype "output"))
      (node (ref "LED2") (pin "4-DIN") (pinfunction "DI_4-DIN") (pintype "input"))
    )
    (net (code "61") (name "Net-(LED2-DO)") (class "Default")
      (node (ref "LED2") (pin "2-DOUT") (pinfunction "DO_2-DOUT") (pintype "output"))
      (node (ref "LED3") (pin "4-DIN") (pinfunction "DI_4-DIN") (pintype "input"))
    )
    (net (code "62") (name "Net-(LED3-DO)") (class "Default")
      (node (ref "LED3") (pin "2-DOUT") (pinfunction "DO_2-DOUT") (pintype "output"))
      (node (ref "LED4") (pin "4-DIN") (pinfunction "DI_4-DIN") (pintype "input"))
    )
    (net (code "63") (name "Net-(LED4-DO)") (class "Default")
      (node (ref "LED4") (pin "2-DOUT") (pinfunction "DO_2-DOUT") (pintype "output"))
      (node (ref "LED5") (pin "4-DIN") (pinfunction "DI_4-DIN") (pintype "input"))
    )
    (net (code "64") (name "Net-(LED5-DO)") (class "Default")
      (node (ref "LED5") (pin "2-DOUT") (pinfunction "DO_2-DOUT") (pintype "output"))
      (node (ref "LED6") (pin "4-DIN") (pinfunction "DI_4-DIN") (pintype "input"))
    )
    (net (code "65") (name "Net-(M.PERC1-PadA)") (class "Default")
      (node (ref "M.PERC1") (pin "A") (pinfunction "A_A") (pintype "output"))
      (node (ref "R27") (pin "1") (pinfunction "1_1") (pintype "passive"))
    )
    (net (code "66") (name "Net-(M.PERC1-PadDP)") (class "Default")
      (node (ref "M.PERC1") (pin "DP") (pinfunction "DP_DP") (pintype "output"))
      (node (ref "M.PERC10") (pin "DP") (pinfunction "DP_DP") (pintype "output"))
      (node (ref "ORA1") (pin "DP") (pinfunction "DP_DP") (pintype "output"))
      (node (ref "ORA10") (pin "DP") (pinfunction "DP_DP") (pintype "output"))
      (node (ref "PERC1") (pin "DP") (pinfunction "DP_DP") (pintype "output"))
      (node (ref "PERC10") (pin "DP") (pinfunction "DP_DP") (pintype "output"))
      (node (ref "T10") (pin "C") (pinfunction "C_C") (pintype "passive"))
    )
    (net (code "67") (name "Net-(M.PERC10-PadA)") (class "Default")
      (node (ref "M.PERC10") (pin "A") (pinfunction "A_A") (pintype "output"))
      (node (ref "R28") (pin "1") (pinfunction "1_1") (pintype "passive"))
    )
    (net (code "68") (name "Net-(ORA1-PadA)") (class "Default")
      (node (ref "ORA1") (pin "A") (pinfunction "A_A") (pintype "output"))
      (node (ref "R4") (pin "1") (pinfunction "1_1") (pintype "passive"))
    )
    (net (code "69") (name "Net-(ORA10-PadA)") (class "Default")
      (node (ref "ORA10") (pin "A") (pinfunction "A_A") (pintype "output"))
      (node (ref "R5") (pin "1") (pinfunction "1_1") (pintype "passive"))
    )
    (net (code "70") (name "Net-(PERC1-PadA)") (class "Default")
      (node (ref "PERC1") (pin "A") (pinfunction "A_A") (pintype "output"))
      (node (ref "R1") (pin "1") (pinfunction "1_1") (pintype "passive"))
    )
    (net (code "71") (name "Net-(PERC10-PadA)") (class "Default")
      (node (ref "PERC10") (pin "A") (pinfunction "A_A") (pintype "output"))
      (node (ref "R2") (pin "1") (pinfunction "1_1") (pintype "passive"))
    )
    (net (code "72") (name "Net-(Q2-X1)") (class "Default")
      (node (ref "C21") (pin "1") (pinfunction "1_1") (pintype "passive"))
      (node (ref "Q2") (pin "1") (pinfunction "X1_1") (pintype "bidirectional"))
      (node (ref "U$1") (pin "7") (pinfunction "XI_7") (pintype "bidirectional"))
    )
    (net (code "73") (name "Net-(Q2-X2)") (class "Default")
      (node (ref "C20") (pin "2") (pinfunction "2_2") (pintype "passive"))
      (node (ref "Q2") (pin "3") (pinfunction "X2_3") (pintype "bidirectional"))
      (node (ref "U$1") (pin "8") (pinfunction "XO_8") (pintype "bidirectional"))
    )
    (net (code "74") (name "Net-(R1-Pad2)") (class "Default")
      (node (ref "R1") (pin "2") (pinfunction "2_2") (pintype "passive"))
      (node (ref "T5") (pin "C") (pinfunction "C_C") (pintype "passive"))
    )
    (net (code "75") (name "Net-(R2-Pad2)") (class "Default")
      (node (ref "R2") (pin "2") (pinfunction "2_2") (pintype "passive"))
      (node (ref "T6") (pin "C") (pinfunction "C_C") (pintype "passive"))
    )
    (net (code "76") (name "Net-(R4-Pad2)") (class "Default")
      (node (ref "R4") (pin "2") (pinfunction "2_2") (pintype "passive"))
      (node (ref "T7") (pin "C") (pinfunction "C_C") (pintype "passive"))
    )
    (net (code "77") (name "Net-(R5-Pad2)") (class "Default")
      (node (ref "R5") (pin "2") (pinfunction "2_2") (pintype "passive"))
      (node (ref "T8") (pin "C") (pinfunction "C_C") (pintype "passive"))
    )
    (net (code "78") (name "Net-(R10-Pad1)") (class "Default")
      (node (ref "R10") (pin "1") (pinfunction "1_1") (pintype "passive"))
      (node (ref "T1") (pin "C") (pinfunction "C_C") (pintype "passive"))
    )
    (net (code "79") (name "Net-(R10-Pad2)") (class "Default")
      (node (ref "R10") (pin "2") (pinfunction "2_2") (pintype "passive"))
      (node (ref "R9") (pin "1") (pinfunction "1_1") (pintype "passive"))
      (node (ref "T5") (pin "B") (pinfunction "B_B") (pintype "passive"))
    )
    (net (code "80") (name "Net-(R11-Pad1)") (class "Default")
      (node (ref "R11") (pin "1") (pinfunction "1_1") (pintype "passive"))
      (node (ref "T2") (pin "C") (pinfunction "C_C") (pintype "passive"))
    )
    (net (code "81") (name "Net-(R11-Pad2)") (class "Default")
      (node (ref "R11") (pin "2") (pinfunction "2_2") (pintype "passive"))
      (node (ref "R6") (pin "1") (pinfunction "1_1") (pintype "passive"))
      (node (ref "T6") (pin "B") (pinfunction "B_B") (pintype "passive"))
    )
    (net (code "82") (name "Net-(R12-Pad1)") (class "Default")
      (node (ref "R12") (pin "1") (pinfunction "1_1") (pintype "passive"))
      (node (ref "T3") (pin "C") (pinfunction "C_C") (pintype "passive"))
    )
    (net (code "83") (name "Net-(R12-Pad2)") (class "Default")
      (node (ref "R12") (pin "2") (pinfunction "2_2") (pintype "passive"))
      (node (ref "R7") (pin "1") (pinfunction "1_1") (pintype "passive"))
      (node (ref "T7") (pin "B") (pinfunction "B_B") (pintype "passive"))
    )
    (net (code "84") (name "Net-(R13-Pad1)") (class "Default")
      (node (ref "R13") (pin "1") (pinfunction "1_1") (pintype "passive"))
      (node (ref "T4") (pin "C") (pinfunction "C_C") (pintype "passive"))
    )
    (net (code "85") (name "Net-(R13-Pad2)") (class "Default")
      (node (ref "R13") (pin "2") (pinfunction "2_2") (pintype "passive"))
      (node (ref "R8") (pin "1") (pinfunction "1_1") (pintype "passive"))
      (node (ref "T8") (pin "B") (pinfunction "B_B") (pintype "passive"))
    )
    (net (code "86") (name "Net-(R14-Pad2)") (class "Default")
      (node (ref "R14") (pin "2") (pinfunction "2_2") (pintype "passive"))
      (node (ref "T1") (pin "B") (pinfunction "B_B") (pintype "passive"))
    )
    (net (code "87") (name "Net-(R15-Pad2)") (class "Default")
      (node (ref "R15") (pin "2") (pinfunction "2_2") (pintype "passive"))
      (node (ref "T2") (pin "B") (pinfunction "B_B") (pintype "passive"))
    )
    (net (code "88") (name "Net-(R19-PadA)") (class "Default")
      (node (ref "R19") (pin "A") (pinfunction "A_A") (pintype "passive"))
      (node (ref "R21") (pin "2") (pinfunction "2_2") (pintype "passive"))
    )
    (net (code "89") (name "Net-(R19-PadE)") (class "Default")
      (node (ref "R19") (pin "E") (pinfunction "E_E") (pintype "passive"))
      (node (ref "R20") (pin "1") (pinfunction "1_1") (pintype "passive"))
    )
    (net (code "90") (name "Net-(R19-PadS)") (class "Default")
      (node (ref "R19") (pin "S") (pinfunction "S_S") (pintype "passive"))
      (node (ref "T9") (pin "B") (pinfunction "B_B") (pintype "passive"))
    )
    (net (code "91") (name "Net-(R22-Pad2)") (class "Default")
      (node (ref "R22") (pin "2") (pinfunction "2_2") (pintype "passive"))
      (node (ref "T3") (pin "B") (pinfunction "B_B") (pintype "passive"))
    )
    (net (code "92") (name "Net-(R23-Pad2)") (class "Default")
      (node (ref "R23") (pin "2") (pinfunction "2_2") (pintype "passive"))
      (node (ref "T4") (pin "B") (pinfunction "B_B") (pintype "passive"))
    )
    (net (code "93") (name "Net-(R24-Pad2)") (class "Default")
      (node (ref "R24") (pin "2") (pinfunction "2_2") (pintype "passive"))
      (node (ref "T10") (pin "B") (pinfunction "B_B") (pintype "passive"))
    )
    (net (code "94") (name "Net-(R25-Pad1)") (class "Default")
      (node (ref "R25") (pin "1") (pinfunction "1_1") (pintype "passive"))
      (node (ref "R35") (pin "A") (pinfunction "A_A") (pintype "passive"))
    )
    (net (code "95") (name "Net-(R27-Pad2)") (class "Default")
      (node (ref "R27") (pin "2") (pinfunction "2_2") (pintype "passive"))
      (node (ref "T13") (pin "C") (pinfunction "C_C") (pintype "passive"))
    )
    (net (code "96") (name "Net-(R28-Pad2)") (class "Default")
      (node (ref "R28") (pin "2") (pinfunction "2_2") (pintype "passive"))
      (node (ref "T14") (pin "C") (pinfunction "C_C") (pintype "passive"))
    )
    (net (code "97") (name "Net-(R29-Pad1)") (class "Default")
      (node (ref "R29") (pin "1") (pinfunction "1_1") (pintype "passive"))
      (node (ref "R30") (pin "2") (pinfunction "2_2") (pintype "passive"))
      (node (ref "T13") (pin "B") (pinfunction "B_B") (pintype "passive"))
    )
    (net (code "98") (name "Net-(R30-Pad1)") (class "Default")
      (node (ref "R30") (pin "1") (pinfunction "1_1") (pintype "passive"))
      (node (ref "T11") (pin "C") (pinfunction "C_C") (pintype "passive"))
    )
    (net (code "99") (name "Net-(R31-Pad2)") (class "Default")
      (node (ref "R31") (pin "2") (pinfunction "2_2") (pintype "passive"))
      (node (ref "T11") (pin "B") (pinfunction "B_B") (pintype "passive"))
    )
    (net (code "100") (name "Net-(R32-Pad2)") (class "Default")
      (node (ref "R32") (pin "2") (pinfunction "2_2") (pintype "passive"))
      (node (ref "T12") (pin "B") (pinfunction "B_B") (pintype "passive"))
    )
    (net (code "101") (name "Net-(R33-Pad1)") (class "Default")
      (node (ref "R33") (pin "1") (pinfunction "1_1") (pintype "passive"))
      (node (ref "T12") (pin "C") (pinfunction "C_C") (pintype "passive"))
    )
    (net (code "102") (name "Net-(R33-Pad2)") (class "Default")
      (node (ref "R33") (pin "2") (pinfunction "2_2") (pintype "passive"))
      (node (ref "R34") (pin "1") (pinfunction "1_1") (pintype "passive"))
      (node (ref "T14") (pin "B") (pinfunction "B_B") (pintype "passive"))
    )
    (net (code "103") (name "Net-(R39-Pad1)") (class "Default")
      (node (ref "R39") (pin "1") (pinfunction "1_1") (pintype "passive"))
      (node (ref "X1") (pin "2") (pinfunction "2_2") (pintype "passive"))
    )
    (net (code "104") (name "Net-(R40-Pad1)") (class "Default")
      (node (ref "R40") (pin "1") (pinfunction "1_1") (pintype "passive"))
      (node (ref "X1") (pin "3") (pinfunction "3_3") (pintype "passive"))
    )
    (net (code "105") (name "Net-(RX/TXB-S)") (class "Default")
      (node (ref "RX/TX") (pin "P$2") (pinfunction "S_P$2") (pintype "passive"))
      (node (ref "U$2") (pin "P$22") (pinfunction "TX_P$22") (pintype "bidirectional"))
    )
    (net (code "106") (name "Net-(RX/TXC-S)") (class "Default")
      (node (ref "RX/TX") (pin "P$3") (pinfunction "S_P$3") (pintype "passive"))
      (node (ref "U$2") (pin "P$24") (pinfunction "RX_P$24") (pintype "bidirectional"))
    )
    (net (code "107") (name "Net-(S1A-S)") (class "Default")
      (node (ref "S1") (pin "P$1") (pinfunction "S_P$1") (pintype "passive"))
      (node (ref "U$2") (pin "P$7") (pinfunction "GPIO26_P$7") (pintype "bidirectional"))
    )
    (net (code "108") (name "Net-(S1B-S)") (class "Default")
      (node (ref "S1") (pin "P$2") (pinfunction "S_P$2") (pintype "passive"))
      (node (ref "U$2") (pin "P$8") (pinfunction "GPIO25_P$8") (pintype "bidirectional"))
    )
    (net (code "109") (name "Net-(SA-S)") (class "Default")
      (node (ref "R37") (pin "1") (pinfunction "1_1") (pintype "passive"))
      (node (ref "S") (pin "P$1") (pinfunction "S_P$1") (pintype "passive"))
      (node (ref "U$2") (pin "P$1") (pinfunction "SVN_P$1") (pintype "bidirectional"))
    )
    (net (code "110") (name "Net-(SB-S)") (class "Default")
      (node (ref "R36") (pin "1") (pinfunction "1_1") (pintype "passive"))
      (node (ref "S") (pin "P$2") (pinfunction "S_P$2") (pintype "passive"))
      (node (ref "U$2") (pin "P$2") (pinfunction "SVP_P$2") (pintype "bidirectional"))
    )
    (net (code "111") (name "Net-(SG1-2)") (class "Default")
      (node (ref "SG1") (pin "-") (pinfunction "2_-") (pintype "passive"))
      (node (ref "T16") (pin "C") (pinfunction "C_C") (pintype "passive"))
    )
    (net (code "112") (name "Net-(SZA-S)") (class "Default")
      (node (ref "M.PERC1") (pin "K4") (pinfunction "K4_K4") (pintype "output"))
      (node (ref "M.PERC10") (pin "K4") (pinfunction "K4_K4") (pintype "output"))
      (node (ref "ORA1") (pin "K4") (pinfunction "K4_K4") (pintype "output"))
      (node (ref "ORA10") (pin "K4") (pinfunction "K4_K4") (pintype "output"))
      (node (ref "PERC1") (pin "K4") (pinfunction "K4_K4") (pintype "output"))
      (node (ref "PERC10") (pin "K4") (pinfunction "K4_K4") (pintype "output"))
      (node (ref "SZ") (pin "P$1") (pinfunction "S_P$1") (pintype "passive"))
    )
    (net (code "113") (name "Net-(SZB-S)") (class "Default")
      (node (ref "M.PERC1") (pin "K3") (pinfunction "K3_K3") (pintype "output"))
      (node (ref "M.PERC10") (pin "K3") (pinfunction "K3_K3") (pintype "output"))
      (node (ref "ORA1") (pin "K3") (pinfunction "K3_K3") (pintype "output"))
      (node (ref "ORA10") (pin "K3") (pinfunction "K3_K3") (pintype "output"))
      (node (ref "PERC1") (pin "K3") (pinfunction "K3_K3") (pintype "output"))
      (node (ref "PERC10") (pin "K3") (pinfunction "K3_K3") (pintype "output"))
      (node (ref "SZ") (pin "P$10") (pinfunction "S_P$10") (pintype "passive"))
    )
    (net (code "114") (name "Net-(SZC-S)") (class "Default")
      (node (ref "M.PERC1") (pin "K5") (pinfunction "K5_K5") (pintype "output"))
      (node (ref "M.PERC10") (pin "K5") (pinfunction "K5_K5") (pintype "output"))
      (node (ref "ORA1") (pin "K5") (pinfunction "K5_K5") (pintype "output"))
      (node (ref "ORA10") (pin "K5") (pinfunction "K5_K5") (pintype "output"))
      (node (ref "PERC1") (pin "K5") (pinfunction "K5_K5") (pintype "output"))
      (node (ref "PERC10") (pin "K5") (pinfunction "K5_K5") (pintype "output"))
      (node (ref "SZ") (pin "P$2") (pinfunction "S_P$2") (pintype "passive"))
    )
    (net (code "115") (name "Net-(SZD-S)") (class "Default")
      (node (ref "M.PERC1") (pin "K9") (pinfunction "K9_K9") (pintype "output"))
      (node (ref "M.PERC10") (pin "K9") (pinfunction "K9_K9") (pintype "output"))
      (node (ref "ORA1") (pin "K9") (pinfunction "K9_K9") (pintype "output"))
      (node (ref "ORA10") (pin "K9") (pinfunction "K9_K9") (pintype "output"))
      (node (ref "PERC1") (pin "K9") (pinfunction "K9_K9") (pintype "output"))
      (node (ref "PERC10") (pin "K9") (pinfunction "K9_K9") (pintype "output"))
      (node (ref "SZ") (pin "P$3") (pinfunction "S_P$3") (pintype "passive"))
    )
    (net (code "116") (name "Net-(SZE-S)") (class "Default")
      (node (ref "M.PERC1") (pin "K2") (pinfunction "K2_K2") (pintype "output"))
      (node (ref "M.PERC10") (pin "K2") (pinfunction "K2_K2") (pintype "output"))
      (node (ref "ORA1") (pin "K2") (pinfunction "K2_K2") (pintype "output"))
      (node (ref "ORA10") (pin "K2") (pinfunction "K2_K2") (pintype "output"))
      (node (ref "PERC1") (pin "K2") (pinfunction "K2_K2") (pintype "output"))
      (node (ref "PERC10") (pin "K2") (pinfunction "K2_K2") (pintype "output"))
      (node (ref "SZ") (pin "P$4") (pinfunction "S_P$4") (pintype "passive"))
    )
    (net (code "117") (name "Net-(SZF-S)") (class "Default")
      (node (ref "M.PERC1") (pin "K0") (pinfunction "K0_K0") (pintype "output"))
      (node (ref "M.PERC10") (pin "K0") (pinfunction "K0_K0") (pintype "output"))
      (node (ref "ORA1") (pin "K0") (pinfunction "K0_K0") (pintype "output"))
      (node (ref "ORA10") (pin "K0") (pinfunction "K0_K0") (pintype "output"))
      (node (ref "PERC1") (pin "K0") (pinfunction "K0_K0") (pintype "output"))
      (node (ref "PERC10") (pin "K0") (pinfunction "K0_K0") (pintype "output"))
      (node (ref "SZ") (pin "P$5") (pinfunction "S_P$5") (pintype "passive"))
    )
    (net (code "118") (name "Net-(SZG-S)") (class "Default")
      (node (ref "M.PERC1") (pin "K1") (pinfunction "K1_K1") (pintype "output"))
      (node (ref "M.PERC10") (pin "K1") (pinfunction "K1_K1") (pintype "output"))
      (node (ref "ORA1") (pin "K1") (pinfunction "K1_K1") (pintype "output"))
      (node (ref "ORA10") (pin "K1") (pinfunction "K1_K1") (pintype "output"))
      (node (ref "PERC1") (pin "K1") (pinfunction "K1_K1") (pintype "output"))
      (node (ref "PERC10") (pin "K1") (pinfunction "K1_K1") (pintype "output"))
      (node (ref "SZ") (pin "P$6") (pinfunction "S_P$6") (pintype "passive"))
    )
    (net (code "119") (name "Net-(SZH-S)") (class "Default")
      (node (ref "M.PERC1") (pin "K8") (pinfunction "K8_K8") (pintype "output"))
      (node (ref "M.PERC10") (pin "K8") (pinfunction "K8_K8") (pintype "output"))
      (node (ref "ORA1") (pin "K8") (pinfunction "K8_K8") (pintype "output"))
      (node (ref "ORA10") (pin "K8") (pinfunction "K8_K8") (pintype "output"))
      (node (ref "PERC1") (pin "K8") (pinfunction "K8_K8") (pintype "output"))
      (node (ref "PERC10") (pin "K8") (pinfunction "K8_K8") (pintype "output"))
      (node (ref "SZ") (pin "P$7") (pinfunction "S_P$7") (pintype "passive"))
    )
    (net (code "120") (name "Net-(SZI-S)") (class "Default")
      (node (ref "M.PERC1") (pin "K7") (pinfunction "K7_K7") (pintype "output"))
      (node (ref "M.PERC10") (pin "K7") (pinfunction "K7_K7") (pintype "output"))
      (node (ref "ORA1") (pin "K7") (pinfunction "K7_K7") (pintype "output"))
      (node (ref "ORA10") (pin "K7") (pinfunction "K7_K7") (pintype "output"))
      (node (ref "PERC1") (pin "K7") (pinfunction "K7_K7") (pintype "output"))
      (node (ref "PERC10") (pin "K7") (pinfunction "K7_K7") (pintype "output"))
      (node (ref "SZ") (pin "P$8") (pinfunction "S_P$8") (pintype "passive"))
    )
    (net (code "121") (name "Net-(SZJ-S)") (class "Default")
      (node (ref "M.PERC1") (pin "K6") (pinfunction "K6_K6") (pintype "output"))
      (node (ref "M.PERC10") (pin "K6") (pinfunction "K6_K6") (pintype "output"))
      (node (ref "ORA1") (pin "K6") (pinfunction "K6_K6") (pintype "output"))
      (node (ref "ORA10") (pin "K6") (pinfunction "K6_K6") (pintype "output"))
      (node (ref "PERC1") (pin "K6") (pinfunction "K6_K6") (pintype "output"))
      (node (ref "PERC10") (pin "K6") (pinfunction "K6_K6") (pintype "output"))
      (node (ref "SZ") (pin "P$9") (pinfunction "S_P$9") (pintype "passive"))
    )
    (net (code "122") (name "Net-(T15A-B)") (class "Default")
      (node (ref "T15") (pin "2") (pinfunction "B_2") (pintype "passive"))
      (node (ref "T15") (pin "4") (pinfunction "E_4") (pintype "passive"))
      (node (ref "U$1") (pin "14") (pinfunction "RTS_14") (pintype "bidirectional"))
    )
    (net (code "123") (name "Net-(T15A-E)") (class "Default")
      (node (ref "T15") (pin "1") (pinfunction "E_1") (pintype "passive"))
      (node (ref "T15") (pin "5") (pinfunction "B_5") (pintype "passive"))
      (node (ref "U$1") (pin "13") (pinfunction "DTR_13") (pintype "bidirectional"))
    )
    (net (code "124") (name "Net-(U$1-D+)") (class "Default")
      (node (ref "R40") (pin "2") (pinfunction "2_2") (pintype "passive"))
      (node (ref "U$1") (pin "5") (pinfunction "D+_5") (pintype "bidirectional"))
    )
    (net (code "125") (name "Net-(U$1-D-)") (class "Default")
      (node (ref "R39") (pin "2") (pinfunction "2_2") (pintype "passive"))
      (node (ref "U$1") (pin "6") (pinfunction "D-_6") (pintype "bidirectional"))
    )
    (net (code "126") (name "Net-(U$2-GPIO32)") (class "Default")
      (node (ref "J1") (pin "2") (pinfunction "2_2") (pintype "passive"))
      (node (ref "R43") (pin "1") (pinfunction "1_1") (pintype "passive"))
      (node (ref "U$2") (pin "P$6") (pinfunction "GPIO32_P$6") (pintype "bidirectional"))
    )
    (net (code "127") (name "Net-(U$2-GPIO33)") (class "Default")
      (node (ref "T16") (pin "B") (pinfunction "B_B") (pintype "passive"))
      (node (ref "U$2") (pin "P$5") (pinfunction "GPIO33_P$5") (pintype "bidirectional"))
    )
    (net (code "128") (name "unconnected-(IC6-DOUT-Pad2)") (class "Default")
      (node (ref "IC6") (pin "2") (pinfunction "DOUT_2") (pintype "output"))
    )
    (net (code "129") (name "unconnected-(IC6-OUT3-Pad23)") (class "Default")
      (node (ref "IC6") (pin "23") (pinfunction "OUT3_23") (pintype "output"))
    )
    (net (code "130") (name "unconnected-(IC6-OUT4-Pad22)") (class "Default")
      (node (ref "IC6") (pin "22") (pinfunction "OUT4_22") (pintype "output"))
    )
    (net (code "131") (name "unconnected-(IC6-OUT5-Pad21)") (class "Default")
      (node (ref "IC6") (pin "21") (pinfunction "OUT5_21") (pintype "output"))
    )
    (net (code "132") (name "unconnected-(IC6-OUT6-Pad20)") (class "Default")
      (node (ref "IC6") (pin "20") (pinfunction "OUT6_20") (pintype "output"))
    )
    (net (code "133") (name "unconnected-(LED6-DO-Pad2-DOUT)") (class "Default")
      (node (ref "LED6") (pin "2-DOUT") (pinfunction "DO_2-DOUT") (pintype "output"))
    )
    (net (code "134") (name "unconnected-(U$1-CTS-Pad9)") (class "Default")
      (node (ref "U$1") (pin "9") (pinfunction "CTS_9") (pintype "bidirectional"))
    )
    (net (code "135") (name "unconnected-(U$1-DCD-Pad12)") (class "Default")
      (node (ref "U$1") (pin "12") (pinfunction "DCD_12") (pintype "bidirectional"))
    )
    (net (code "136") (name "unconnected-(U$1-DSR-Pad10)") (class "Default")
      (node (ref "U$1") (pin "10") (pinfunction "DSR_10") (pintype "bidirectional"))
    )
    (net (code "137") (name "unconnected-(U$1-RI-Pad11)") (class "Default")
      (node (ref "U$1") (pin "11") (pinfunction "RI_11") (pintype "bidirectional"))
    )
    (net (code "138") (name "unconnected-(U$1-RS232-Pad15)") (class "Default")
      (node (ref "U$1") (pin "15") (pinfunction "RS232_15") (pintype "bidirectional"))
    )
    (net (code "139") (name "unconnected-(U$1-RX-Pad3)") (class "Default")
      (node (ref "U$1") (pin "3") (pinfunction "RX_3") (pintype "bidirectional"))
    )
    (net (code "140") (name "unconnected-(U$1-TX-Pad2)") (class "Default")
      (node (ref "U$1") (pin "2") (pinfunction "TX_2") (pintype "bidirectional"))
    )
    (net (code "141") (name "unconnected-(U$1-V3-Pad4)") (class "Default")
      (node (ref "U$1") (pin "4") (pinfunction "V3_4") (pintype "bidirectional"))
    )
    (net (code "142") (name "unconnected-(U$2-CLK-PadP$15)") (class "Default")
      (node (ref "U$2") (pin "P$15") (pinfunction "CLK_P$15") (pintype "bidirectional"))
    )
    (net (code "143") (name "unconnected-(U$2-CMD-PadP$16)") (class "Default")
      (node (ref "U$2") (pin "P$16") (pinfunction "CMD_P$16") (pintype "bidirectional"))
    )
    (net (code "144") (name "unconnected-(U$2-GPIO34-PadP$4)") (class "Default")
      (node (ref "U$2") (pin "P$4") (pinfunction "GPIO34_P$4") (pintype "bidirectional"))
    )
    (net (code "145") (name "unconnected-(U$2-GPIO35-PadP$3)") (class "Default")
      (node (ref "U$2") (pin "P$3") (pinfunction "GPIO35_P$3") (pintype "bidirectional"))
    )
    (net (code "146") (name "unconnected-(U$2-SD0-PadP$18)") (class "Default")
      (node (ref "U$2") (pin "P$18") (pinfunction "SD0_P$18") (pintype "bidirectional"))
    )
    (net (code "147") (name "unconnected-(U$2-SD1-PadP$17)") (class "Default")
      (node (ref "U$2") (pin "P$17") (pinfunction "SD1_P$17") (pintype "bidirectional"))
    )
    (net (code "148") (name "unconnected-(U$2-SD2-PadP$14)") (class "Default")
      (node (ref "U$2") (pin "P$14") (pinfunction "SD2_P$14") (pintype "bidirectional"))
    )
    (net (code "149") (name "unconnected-(U$2-SD3-PadP$13)") (class "Default")
      (node (ref "U$2") (pin "P$13") (pinfunction "SD3_P$13") (pintype "bidirectional"))
    )
    (net (code "150") (name "unconnected-(X1-Pad4)") (class "Default")
      (node (ref "X1") (pin "4") (pinfunction "4_4") (pintype "passive"))
    )
  )
)
